# SDRAM_32_BGA.net
KiCad netlist of a schematic drawn in Altium Designer
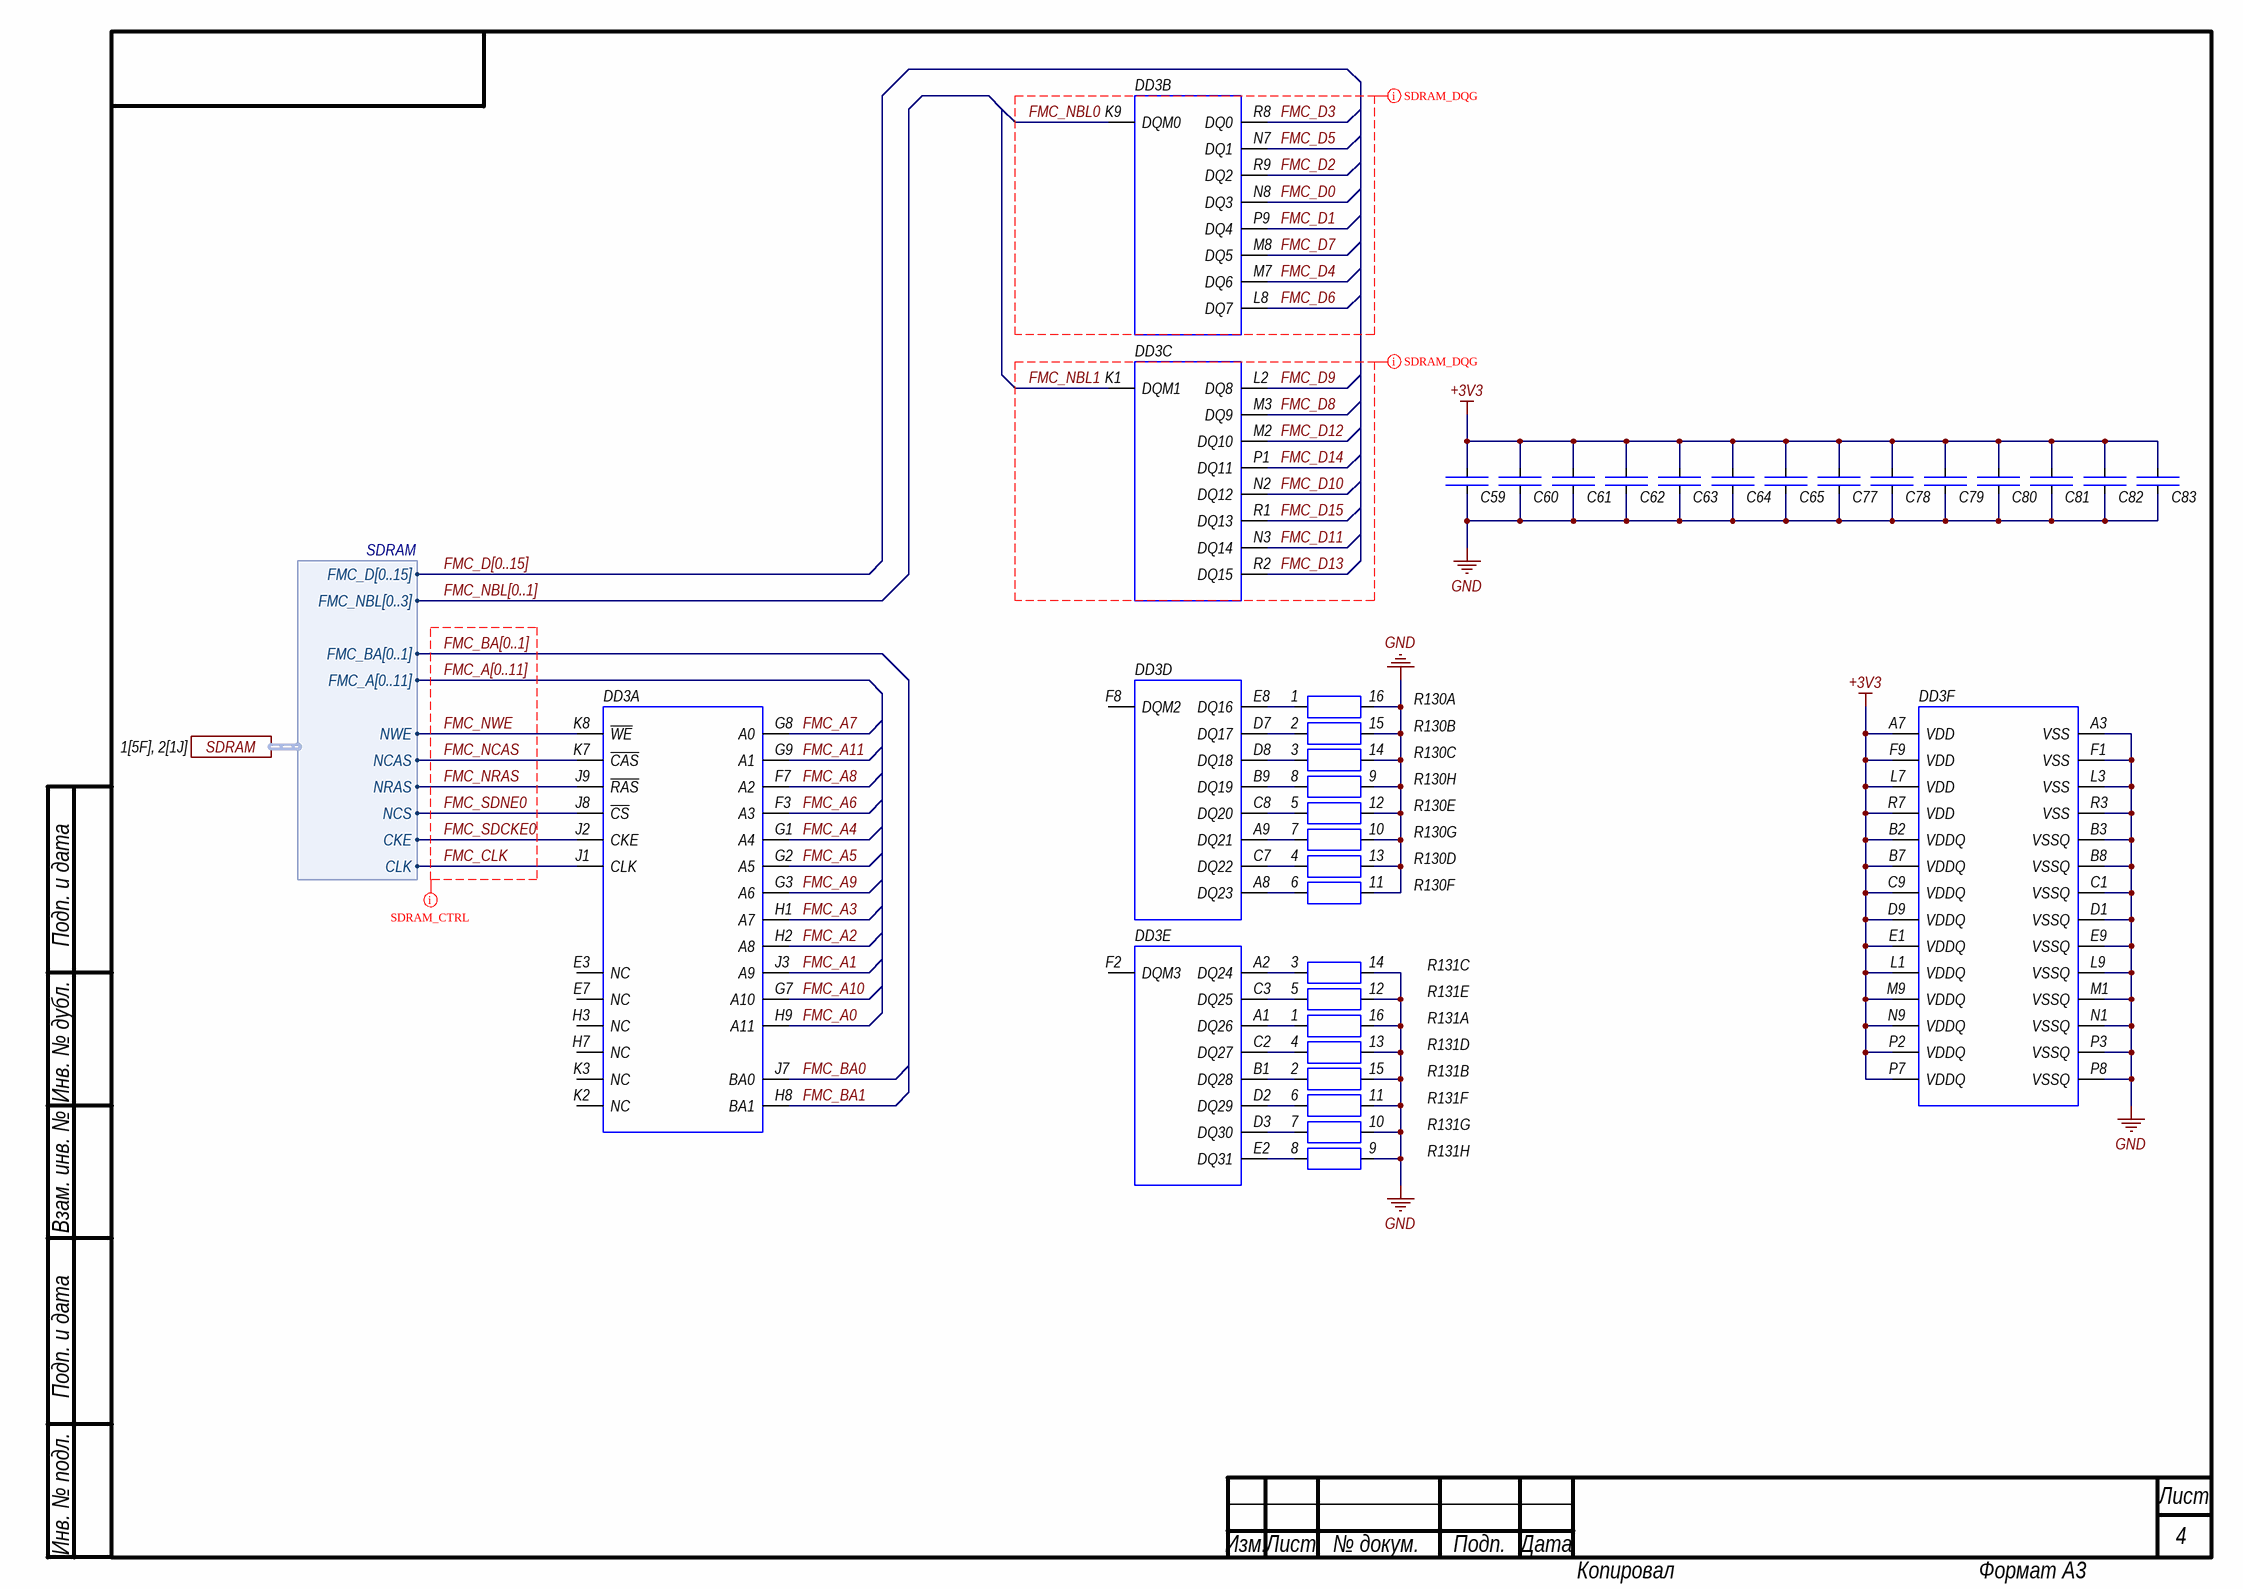
[diagram p0: SDRAM_32_BGA.SchDoc]

(export (version "E")
  (design (tool "Eeschema 10.0.6"))
  (components
    (comp (ref "C59")
      (value "Конденсатор керам. ЧИП X5R, 10%, 0402, 0.1 мкФ")
      (footprint "Capacitor 0402")
      (description "Cap Ceramic 0.1uF 50V X5R 10% Pad SMD 0402 85C T/R")
      (fields (field (name "VOLTAGE") "50V") (field (name "MANUFACTURER") "Murata Manufacturing"))
      (libsource (lib "Eleps server") (part "Nonpolar Capacitor"))
    )
    (comp (ref "C60")
      (value "Конденсатор керам. ЧИП X5R, 10%, 0402, 0.1 мкФ")
      (footprint "Capacitor 0402")
      (description "Cap Ceramic 0.1uF 50V X5R 10% Pad SMD 0402 85C T/R")
      (fields (field (name "VOLTAGE") "50V") (field (name "MANUFACTURER") "Murata Manufacturing"))
      (libsource (lib "Eleps server") (part "Nonpolar Capacitor"))
    )
    (comp (ref "C61")
      (value "Конденсатор керам. ЧИП X5R, 10%, 0402, 0.1 мкФ")
      (footprint "Capacitor 0402")
      (description "Cap Ceramic 0.1uF 50V X5R 10% Pad SMD 0402 85C T/R")
      (fields (field (name "VOLTAGE") "50V") (field (name "MANUFACTURER") "Murata Manufacturing"))
      (libsource (lib "Eleps server") (part "Nonpolar Capacitor"))
    )
    (comp (ref "C62")
      (value "Конденсатор керам. ЧИП X5R, 10%, 0402, 0.1 мкФ")
      (footprint "Capacitor 0402")
      (description "Cap Ceramic 0.1uF 50V X5R 10% Pad SMD 0402 85C T/R")
      (fields (field (name "VOLTAGE") "50V") (field (name "MANUFACTURER") "Murata Manufacturing"))
      (libsource (lib "Eleps server") (part "Nonpolar Capacitor"))
    )
    (comp (ref "C63")
      (value "Конденсатор керам. ЧИП X5R, 10%, 0402, 0.1 мкФ")
      (footprint "Capacitor 0402")
      (description "Cap Ceramic 0.1uF 50V X5R 10% Pad SMD 0402 85C T/R")
      (fields (field (name "VOLTAGE") "50V") (field (name "MANUFACTURER") "Murata Manufacturing"))
      (libsource (lib "Eleps server") (part "Nonpolar Capacitor"))
    )
    (comp (ref "C64")
      (value "Конденсатор керам. ЧИП X5R, 10%, 0402, 0.1 мкФ")
      (footprint "Capacitor 0402")
      (description "Cap Ceramic 0.1uF 50V X5R 10% Pad SMD 0402 85C T/R")
      (fields (field (name "VOLTAGE") "50V") (field (name "MANUFACTURER") "Murata Manufacturing"))
      (libsource (lib "Eleps server") (part "Nonpolar Capacitor"))
    )
    (comp (ref "C65")
      (value "Конденсатор керам. ЧИП X5R, 10%, 0402, 0.1 мкФ")
      (footprint "Capacitor 0402")
      (description "Cap Ceramic 0.1uF 50V X5R 10% Pad SMD 0402 85C T/R")
      (fields (field (name "VOLTAGE") "50V") (field (name "MANUFACTURER") "Murata Manufacturing"))
      (libsource (lib "Eleps server") (part "Nonpolar Capacitor"))
    )
    (comp (ref "C77")
      (value "Конденсатор керам. ЧИП X5R, 10%, 0402, 0.1 мкФ")
      (footprint "Capacitor 0402")
      (description "Cap Ceramic 0.1uF 50V X5R 10% Pad SMD 0402 85C T/R")
      (fields (field (name "VOLTAGE") "50V") (field (name "MANUFACTURER") "Murata Manufacturing"))
      (libsource (lib "Eleps server") (part "Nonpolar Capacitor"))
    )
    (comp (ref "C78")
      (value "Конденсатор керам. ЧИП X5R, 10%, 0402, 0.1 мкФ")
      (footprint "Capacitor 0402")
      (description "Cap Ceramic 0.1uF 50V X5R 10% Pad SMD 0402 85C T/R")
      (fields (field (name "VOLTAGE") "50V") (field (name "MANUFACTURER") "Murata Manufacturing"))
      (libsource (lib "Eleps server") (part "Nonpolar Capacitor"))
    )
    (comp (ref "C79")
      (value "Конденсатор керам. ЧИП X5R, 10%, 0402, 0.1 мкФ")
      (footprint "Capacitor 0402")
      (description "Cap Ceramic 0.1uF 50V X5R 10% Pad SMD 0402 85C T/R")
      (fields (field (name "VOLTAGE") "50V") (field (name "MANUFACTURER") "Murata Manufacturing"))
      (libsource (lib "Eleps server") (part "Nonpolar Capacitor"))
    )
    (comp (ref "C80")
      (value "Конденсатор керам. ЧИП X5R, 10%, 0402, 0.1 мкФ")
      (footprint "Capacitor 0402")
      (description "Cap Ceramic 0.1uF 50V X5R 10% Pad SMD 0402 85C T/R")
      (fields (field (name "VOLTAGE") "50V") (field (name "MANUFACTURER") "Murata Manufacturing"))
      (libsource (lib "Eleps server") (part "Nonpolar Capacitor"))
    )
    (comp (ref "C81")
      (value "Конденсатор керам. ЧИП X5R, 10%, 0402, 0.1 мкФ")
      (footprint "Capacitor 0402")
      (description "Cap Ceramic 0.1uF 50V X5R 10% Pad SMD 0402 85C T/R")
      (fields (field (name "VOLTAGE") "50V") (field (name "MANUFACTURER") "Murata Manufacturing"))
      (libsource (lib "Eleps server") (part "Nonpolar Capacitor"))
    )
    (comp (ref "C82")
      (value "Конденсатор керам. ЧИП X5R, 10%, 0402, 0.1 мкФ")
      (footprint "Capacitor 0402")
      (description "Cap Ceramic 0.1uF 50V X5R 10% Pad SMD 0402 85C T/R")
      (fields (field (name "VOLTAGE") "50V") (field (name "MANUFACTURER") "Murata Manufacturing"))
      (libsource (lib "Eleps server") (part "Nonpolar Capacitor"))
    )
    (comp (ref "C83")
      (value "Конденсатор керам. ЧИП X5R, 10%, 0402, 0.1 мкФ")
      (footprint "Capacitor 0402")
      (description "Cap Ceramic 0.1uF 50V X5R 10% Pad SMD 0402 85C T/R")
      (fields (field (name "VOLTAGE") "50V") (field (name "MANUFACTURER") "Murata Manufacturing"))
      (libsource (lib "Eleps server") (part "Nonpolar Capacitor"))
    )
    (comp (ref "DD3")
      (value "Микросхема IS42S32400F-6BL")
      (footprint "BGA90C80P9X15_800X1300X120")
      (description "128Mb (4M x 32) Synchronous DRAM")
      (fields (field (name "PART NUMBER") "IS42S32400F-6BL"))
      (libsource (lib "PhLib") (part "IS42S32400F-6BL"))
    )
    (comp (ref "R130")
      (value "8-Resistor")
      (footprint "RESNET_1506-16_CONVEX")
      (fields (field (name "PART NUMBER") "EXB2HV103JV") (field (name "MANUFACTURER") "Panasonic"))
      (libsource (lib "PhLib") (part "8-Resistor"))
    )
    (comp (ref "R131")
      (value "8-Resistor")
      (footprint "RESNET_1506-16_CONVEX")
      (fields (field (name "PART NUMBER") "EXB2HV103JV") (field (name "MANUFACTURER") "Panasonic"))
      (libsource (lib "PhLib") (part "8-Resistor"))
    )
  )
  (nets
    (net (code "2") (name "+3V3") (class "Default")
      (node (ref "C59") (pin "1") (pinfunction "1_1") (pintype "passive"))
      (node (ref "C60") (pin "1") (pinfunction "1_1") (pintype "passive"))
      (node (ref "C61") (pin "1") (pinfunction "1_1") (pintype "passive"))
      (node (ref "C62") (pin "1") (pinfunction "1_1") (pintype "passive"))
      (node (ref "C63") (pin "1") (pinfunction "1_1") (pintype "passive"))
      (node (ref "C64") (pin "1") (pinfunction "1_1") (pintype "passive"))
      (node (ref "C65") (pin "1") (pinfunction "1_1") (pintype "passive"))
      (node (ref "C77") (pin "1") (pinfunction "1_1") (pintype "passive"))
      (node (ref "C78") (pin "1") (pinfunction "1_1") (pintype "passive"))
      (node (ref "C79") (pin "1") (pinfunction "1_1") (pintype "passive"))
      (node (ref "C80") (pin "1") (pinfunction "1_1") (pintype "passive"))
      (node (ref "C81") (pin "1") (pinfunction "1_1") (pintype "passive"))
      (node (ref "C82") (pin "1") (pinfunction "1_1") (pintype "passive"))
      (node (ref "C83") (pin "1") (pinfunction "1_1") (pintype "passive"))
      (node (ref "DD3") (pin "A7") (pinfunction "VDD_A7") (pintype "passive"))
      (node (ref "DD3") (pin "B2") (pinfunction "VDDQ_B2") (pintype "passive"))
      (node (ref "DD3") (pin "B7") (pinfunction "VDDQ_B7") (pintype "passive"))
      (node (ref "DD3") (pin "C9") (pinfunction "VDDQ_C9") (pintype "passive"))
      (node (ref "DD3") (pin "D9") (pinfunction "VDDQ_D9") (pintype "passive"))
      (node (ref "DD3") (pin "E1") (pinfunction "VDDQ_E1") (pintype "passive"))
      (node (ref "DD3") (pin "F9") (pinfunction "VDD_F9") (pintype "passive"))
      (node (ref "DD3") (pin "L1") (pinfunction "VDDQ_L1") (pintype "passive"))
      (node (ref "DD3") (pin "L7") (pinfunction "VDD_L7") (pintype "passive"))
      (node (ref "DD3") (pin "M9") (pinfunction "VDDQ_M9") (pintype "passive"))
      (node (ref "DD3") (pin "N9") (pinfunction "VDDQ_N9") (pintype "passive"))
      (node (ref "DD3") (pin "P2") (pinfunction "VDDQ_P2") (pintype "passive"))
      (node (ref "DD3") (pin "P7") (pinfunction "VDDQ_P7") (pintype "passive"))
      (node (ref "DD3") (pin "R7") (pinfunction "VDD_R7") (pintype "passive"))
    )
    (net (code "3") (name "/FMC_A0") (class "Default")
      (node (ref "DD3") (pin "H9") (pinfunction "A11_H9") (pintype "passive"))
    )
    (net (code "4") (name "/FMC_A1") (class "Default")
      (node (ref "DD3") (pin "J3") (pinfunction "A9_J3") (pintype "passive"))
    )
    (net (code "5") (name "/FMC_A2") (class "Default")
      (node (ref "DD3") (pin "H2") (pinfunction "A8_H2") (pintype "passive"))
    )
    (net (code "6") (name "/FMC_A3") (class "Default")
      (node (ref "DD3") (pin "H1") (pinfunction "A7_H1") (pintype "passive"))
    )
    (net (code "7") (name "/FMC_A4") (class "Default")
      (node (ref "DD3") (pin "G1") (pinfunction "A4_G1") (pintype "passive"))
    )
    (net (code "8") (name "/FMC_A5") (class "Default")
      (node (ref "DD3") (pin "G2") (pinfunction "A5_G2") (pintype "passive"))
    )
    (net (code "9") (name "/FMC_A6") (class "Default")
      (node (ref "DD3") (pin "F3") (pinfunction "A3_F3") (pintype "passive"))
    )
    (net (code "10") (name "/FMC_A7") (class "Default")
      (node (ref "DD3") (pin "G8") (pinfunction "A0_G8") (pintype "passive"))
    )
    (net (code "11") (name "/FMC_A8") (class "Default")
      (node (ref "DD3") (pin "F7") (pinfunction "A2_F7") (pintype "passive"))
    )
    (net (code "12") (name "/FMC_A9") (class "Default")
      (node (ref "DD3") (pin "G3") (pinfunction "A6_G3") (pintype "passive"))
    )
    (net (code "13") (name "/FMC_A10") (class "Default")
      (node (ref "DD3") (pin "G7") (pinfunction "A10_G7") (pintype "passive"))
    )
    (net (code "14") (name "/FMC_A11") (class "Default")
      (node (ref "DD3") (pin "G9") (pinfunction "A1_G9") (pintype "passive"))
    )
    (net (code "15") (name "/FMC_BA0") (class "Default")
      (node (ref "DD3") (pin "J7") (pinfunction "BA0_J7") (pintype "passive"))
    )
    (net (code "16") (name "/FMC_BA1") (class "Default")
      (node (ref "DD3") (pin "H8") (pinfunction "BA1_H8") (pintype "passive"))
    )
    (net (code "18") (name "/FMC_CLK") (class "Default")
      (node (ref "DD3") (pin "J1") (pinfunction "CLK_J1") (pintype "passive"))
    )
    (net (code "19") (name "/FMC_D0") (class "Default")
      (node (ref "DD3") (pin "N8") (pinfunction "DQ3_N8") (pintype "passive"))
    )
    (net (code "20") (name "/FMC_D1") (class "Default")
      (node (ref "DD3") (pin "P9") (pinfunction "DQ4_P9") (pintype "passive"))
    )
    (net (code "21") (name "/FMC_D2") (class "Default")
      (node (ref "DD3") (pin "R9") (pinfunction "DQ2_R9") (pintype "passive"))
    )
    (net (code "22") (name "/FMC_D3") (class "Default")
      (node (ref "DD3") (pin "R8") (pinfunction "DQ0_R8") (pintype "passive"))
    )
    (net (code "23") (name "/FMC_D4") (class "Default")
      (node (ref "DD3") (pin "M7") (pinfunction "DQ6_M7") (pintype "passive"))
    )
    (net (code "24") (name "/FMC_D5") (class "Default")
      (node (ref "DD3") (pin "N7") (pinfunction "DQ1_N7") (pintype "passive"))
    )
    (net (code "25") (name "/FMC_D6") (class "Default")
      (node (ref "DD3") (pin "L8") (pinfunction "DQ7_L8") (pintype "passive"))
    )
    (net (code "26") (name "/FMC_D7") (class "Default")
      (node (ref "DD3") (pin "M8") (pinfunction "DQ5_M8") (pintype "passive"))
    )
    (net (code "27") (name "/FMC_D8") (class "Default")
      (node (ref "DD3") (pin "M3") (pinfunction "DQ9_M3") (pintype "passive"))
    )
    (net (code "28") (name "/FMC_D9") (class "Default")
      (node (ref "DD3") (pin "L2") (pinfunction "DQ8_L2") (pintype "passive"))
    )
    (net (code "29") (name "/FMC_D10") (class "Default")
      (node (ref "DD3") (pin "N2") (pinfunction "DQ12_N2") (pintype "passive"))
    )
    (net (code "30") (name "/FMC_D11") (class "Default")
      (node (ref "DD3") (pin "N3") (pinfunction "DQ14_N3") (pintype "passive"))
    )
    (net (code "31") (name "/FMC_D12") (class "Default")
      (node (ref "DD3") (pin "M2") (pinfunction "DQ10_M2") (pintype "passive"))
    )
    (net (code "32") (name "/FMC_D13") (class "Default")
      (node (ref "DD3") (pin "R2") (pinfunction "DQ15_R2") (pintype "passive"))
    )
    (net (code "33") (name "/FMC_D14") (class "Default")
      (node (ref "DD3") (pin "P1") (pinfunction "DQ11_P1") (pintype "passive"))
    )
    (net (code "34") (name "/FMC_D15") (class "Default")
      (node (ref "DD3") (pin "R1") (pinfunction "DQ13_R1") (pintype "passive"))
    )
    (net (code "36") (name "/FMC_NBL0") (class "Default")
      (node (ref "DD3") (pin "K9") (pinfunction "DQM0_K9") (pintype "passive"))
    )
    (net (code "37") (name "/FMC_NBL1") (class "Default")
      (node (ref "DD3") (pin "K1") (pinfunction "DQM1_K1") (pintype "passive"))
    )
    (net (code "39") (name "/FMC_NCAS") (class "Default")
      (node (ref "DD3") (pin "K7") (pinfunction "~{CAS}_K7") (pintype "passive"))
    )
    (net (code "40") (name "/FMC_NRAS") (class "Default")
      (node (ref "DD3") (pin "J9") (pinfunction "~{RAS}_J9") (pintype "passive"))
    )
    (net (code "41") (name "/FMC_NWE") (class "Default")
      (node (ref "DD3") (pin "K8") (pinfunction "~{WE}_K8") (pintype "passive"))
    )
    (net (code "42") (name "/FMC_SDCKE0") (class "Default")
      (node (ref "DD3") (pin "J2") (pinfunction "CKE_J2") (pintype "passive"))
    )
    (net (code "43") (name "/FMC_SDNE0") (class "Default")
      (node (ref "DD3") (pin "J8") (pinfunction "~{CS}_J8") (pintype "passive"))
    )
    (net (code "46") (name "GND") (class "Default")
      (node (ref "C59") (pin "2") (pinfunction "2_2") (pintype "passive"))
      (node (ref "C60") (pin "2") (pinfunction "2_2") (pintype "passive"))
      (node (ref "C61") (pin "2") (pinfunction "2_2") (pintype "passive"))
      (node (ref "C62") (pin "2") (pinfunction "2_2") (pintype "passive"))
      (node (ref "C63") (pin "2") (pinfunction "2_2") (pintype "passive"))
      (node (ref "C64") (pin "2") (pinfunction "2_2") (pintype "passive"))
      (node (ref "C65") (pin "2") (pinfunction "2_2") (pintype "passive"))
      (node (ref "C77") (pin "2") (pinfunction "2_2") (pintype "passive"))
      (node (ref "C78") (pin "2") (pinfunction "2_2") (pintype "passive"))
      (node (ref "C79") (pin "2") (pinfunction "2_2") (pintype "passive"))
      (node (ref "C80") (pin "2") (pinfunction "2_2") (pintype "passive"))
      (node (ref "C81") (pin "2") (pinfunction "2_2") (pintype "passive"))
      (node (ref "C82") (pin "2") (pinfunction "2_2") (pintype "passive"))
      (node (ref "C83") (pin "2") (pinfunction "2_2") (pintype "passive"))
      (node (ref "DD3") (pin "A3") (pinfunction "VSS_A3") (pintype "passive"))
      (node (ref "DD3") (pin "B3") (pinfunction "VSSQ_B3") (pintype "passive"))
      (node (ref "DD3") (pin "B8") (pinfunction "VSSQ_B8") (pintype "passive"))
      (node (ref "DD3") (pin "C1") (pinfunction "VSSQ_C1") (pintype "passive"))
      (node (ref "DD3") (pin "D1") (pinfunction "VSSQ_D1") (pintype "passive"))
      (node (ref "DD3") (pin "E9") (pinfunction "VSSQ_E9") (pintype "passive"))
      (node (ref "DD3") (pin "F1") (pinfunction "VSS_F1") (pintype "passive"))
      (node (ref "DD3") (pin "L3") (pinfunction "VSS_L3") (pintype "passive"))
      (node (ref "DD3") (pin "L9") (pinfunction "VSSQ_L9") (pintype "passive"))
      (node (ref "DD3") (pin "M1") (pinfunction "VSSQ_M1") (pintype "passive"))
      (node (ref "DD3") (pin "N1") (pinfunction "VSSQ_N1") (pintype "passive"))
      (node (ref "DD3") (pin "P3") (pinfunction "VSSQ_P3") (pintype "passive"))
      (node (ref "DD3") (pin "P8") (pinfunction "VSSQ_P8") (pintype "passive"))
      (node (ref "DD3") (pin "R3") (pinfunction "VSS_R3") (pintype "passive"))
      (node (ref "R130") (pin "10") (pintype "passive"))
      (node (ref "R130") (pin "11") (pintype "passive"))
      (node (ref "R130") (pin "12") (pintype "passive"))
      (node (ref "R130") (pin "13") (pintype "passive"))
      (node (ref "R130") (pin "14") (pintype "passive"))
      (node (ref "R130") (pin "15") (pintype "passive"))
      (node (ref "R130") (pin "16") (pintype "passive"))
      (node (ref "R130") (pin "9") (pintype "passive"))
      (node (ref "R131") (pin "10") (pintype "passive"))
      (node (ref "R131") (pin "11") (pintype "passive"))
      (node (ref "R131") (pin "12") (pintype "passive"))
      (node (ref "R131") (pin "13") (pintype "passive"))
      (node (ref "R131") (pin "14") (pintype "passive"))
      (node (ref "R131") (pin "15") (pintype "passive"))
      (node (ref "R131") (pin "16") (pintype "passive"))
      (node (ref "R131") (pin "9") (pintype "passive"))
    )
    (net (code "47") (name "Net-(DD3D-DQ16)") (class "Default")
      (node (ref "DD3") (pin "E8") (pinfunction "DQ16_E8") (pintype "passive"))
      (node (ref "R130") (pin "1") (pintype "passive"))
    )
    (net (code "48") (name "Net-(DD3D-DQ17)") (class "Default")
      (node (ref "DD3") (pin "D7") (pinfunction "DQ17_D7") (pintype "passive"))
      (node (ref "R130") (pin "2") (pintype "passive"))
    )
    (net (code "49") (name "Net-(DD3D-DQ18)") (class "Default")
      (node (ref "DD3") (pin "D8") (pinfunction "DQ18_D8") (pintype "passive"))
      (node (ref "R130") (pin "3") (pintype "passive"))
    )
    (net (code "50") (name "Net-(DD3D-DQ19)") (class "Default")
      (node (ref "DD3") (pin "B9") (pinfunction "DQ19_B9") (pintype "passive"))
      (node (ref "R130") (pin "8") (pintype "passive"))
    )
    (net (code "51") (name "Net-(DD3D-DQ20)") (class "Default")
      (node (ref "DD3") (pin "C8") (pinfunction "DQ20_C8") (pintype "passive"))
      (node (ref "R130") (pin "5") (pintype "passive"))
    )
    (net (code "52") (name "Net-(DD3D-DQ21)") (class "Default")
      (node (ref "DD3") (pin "A9") (pinfunction "DQ21_A9") (pintype "passive"))
      (node (ref "R130") (pin "7") (pintype "passive"))
    )
    (net (code "53") (name "Net-(DD3D-DQ22)") (class "Default")
      (node (ref "DD3") (pin "C7") (pinfunction "DQ22_C7") (pintype "passive"))
      (node (ref "R130") (pin "4") (pintype "passive"))
    )
    (net (code "54") (name "Net-(DD3D-DQ23)") (class "Default")
      (node (ref "DD3") (pin "A8") (pinfunction "DQ23_A8") (pintype "passive"))
      (node (ref "R130") (pin "6") (pintype "passive"))
    )
    (net (code "55") (name "Net-(DD3E-DQ24)") (class "Default")
      (node (ref "DD3") (pin "A2") (pinfunction "DQ24_A2") (pintype "passive"))
      (node (ref "R131") (pin "3") (pintype "passive"))
    )
    (net (code "56") (name "Net-(DD3E-DQ25)") (class "Default")
      (node (ref "DD3") (pin "C3") (pinfunction "DQ25_C3") (pintype "passive"))
      (node (ref "R131") (pin "5") (pintype "passive"))
    )
    (net (code "57") (name "Net-(DD3E-DQ26)") (class "Default")
      (node (ref "DD3") (pin "A1") (pinfunction "DQ26_A1") (pintype "passive"))
      (node (ref "R131") (pin "1") (pintype "passive"))
    )
    (net (code "58") (name "Net-(DD3E-DQ27)") (class "Default")
      (node (ref "DD3") (pin "C2") (pinfunction "DQ27_C2") (pintype "passive"))
      (node (ref "R131") (pin "4") (pintype "passive"))
    )
    (net (code "59") (name "Net-(DD3E-DQ28)") (class "Default")
      (node (ref "DD3") (pin "B1") (pinfunction "DQ28_B1") (pintype "passive"))
      (node (ref "R131") (pin "2") (pintype "passive"))
    )
    (net (code "60") (name "Net-(DD3E-DQ29)") (class "Default")
      (node (ref "DD3") (pin "D2") (pinfunction "DQ29_D2") (pintype "passive"))
      (node (ref "R131") (pin "6") (pintype "passive"))
    )
    (net (code "61") (name "Net-(DD3E-DQ30)") (class "Default")
      (node (ref "DD3") (pin "D3") (pinfunction "DQ30_D3") (pintype "passive"))
      (node (ref "R131") (pin "7") (pintype "passive"))
    )
    (net (code "62") (name "Net-(DD3E-DQ31)") (class "Default")
      (node (ref "DD3") (pin "E2") (pinfunction "DQ31_E2") (pintype "passive"))
      (node (ref "R131") (pin "8") (pintype "passive"))
    )
    (net (code "63") (name "unconnected-(DD3A-NC-PadE3)") (class "Default")
      (node (ref "DD3") (pin "E3") (pinfunction "NC_E3") (pintype "passive"))
    )
    (net (code "64") (name "unconnected-(DD3A-NC-PadE7)") (class "Default")
      (node (ref "DD3") (pin "E7") (pinfunction "NC_E7") (pintype "passive"))
    )
    (net (code "65") (name "unconnected-(DD3A-NC-PadH3)") (class "Default")
      (node (ref "DD3") (pin "H3") (pinfunction "NC_H3") (pintype "passive"))
    )
    (net (code "66") (name "unconnected-(DD3A-NC-PadH7)") (class "Default")
      (node (ref "DD3") (pin "H7") (pinfunction "NC_H7") (pintype "passive"))
    )
    (net (code "67") (name "unconnected-(DD3A-NC-PadK2)") (class "Default")
      (node (ref "DD3") (pin "K2") (pinfunction "NC_K2") (pintype "passive"))
    )
    (net (code "68") (name "unconnected-(DD3A-NC-PadK3)") (class "Default")
      (node (ref "DD3") (pin "K3") (pinfunction "NC_K3") (pintype "passive"))
    )
    (net (code "69") (name "unconnected-(DD3D-DQM2-PadF8)") (class "Default")
      (node (ref "DD3") (pin "F8") (pinfunction "DQM2_F8") (pintype "passive"))
    )
    (net (code "70") (name "unconnected-(DD3E-DQM3-PadF2)") (class "Default")
      (node (ref "DD3") (pin "F2") (pinfunction "DQM3_F2") (pintype "passive"))
    )
  )
)
